# XL_N76E003K1__POWER_V17.net
KiCad netlist of a schematic drawn in Altium Designer
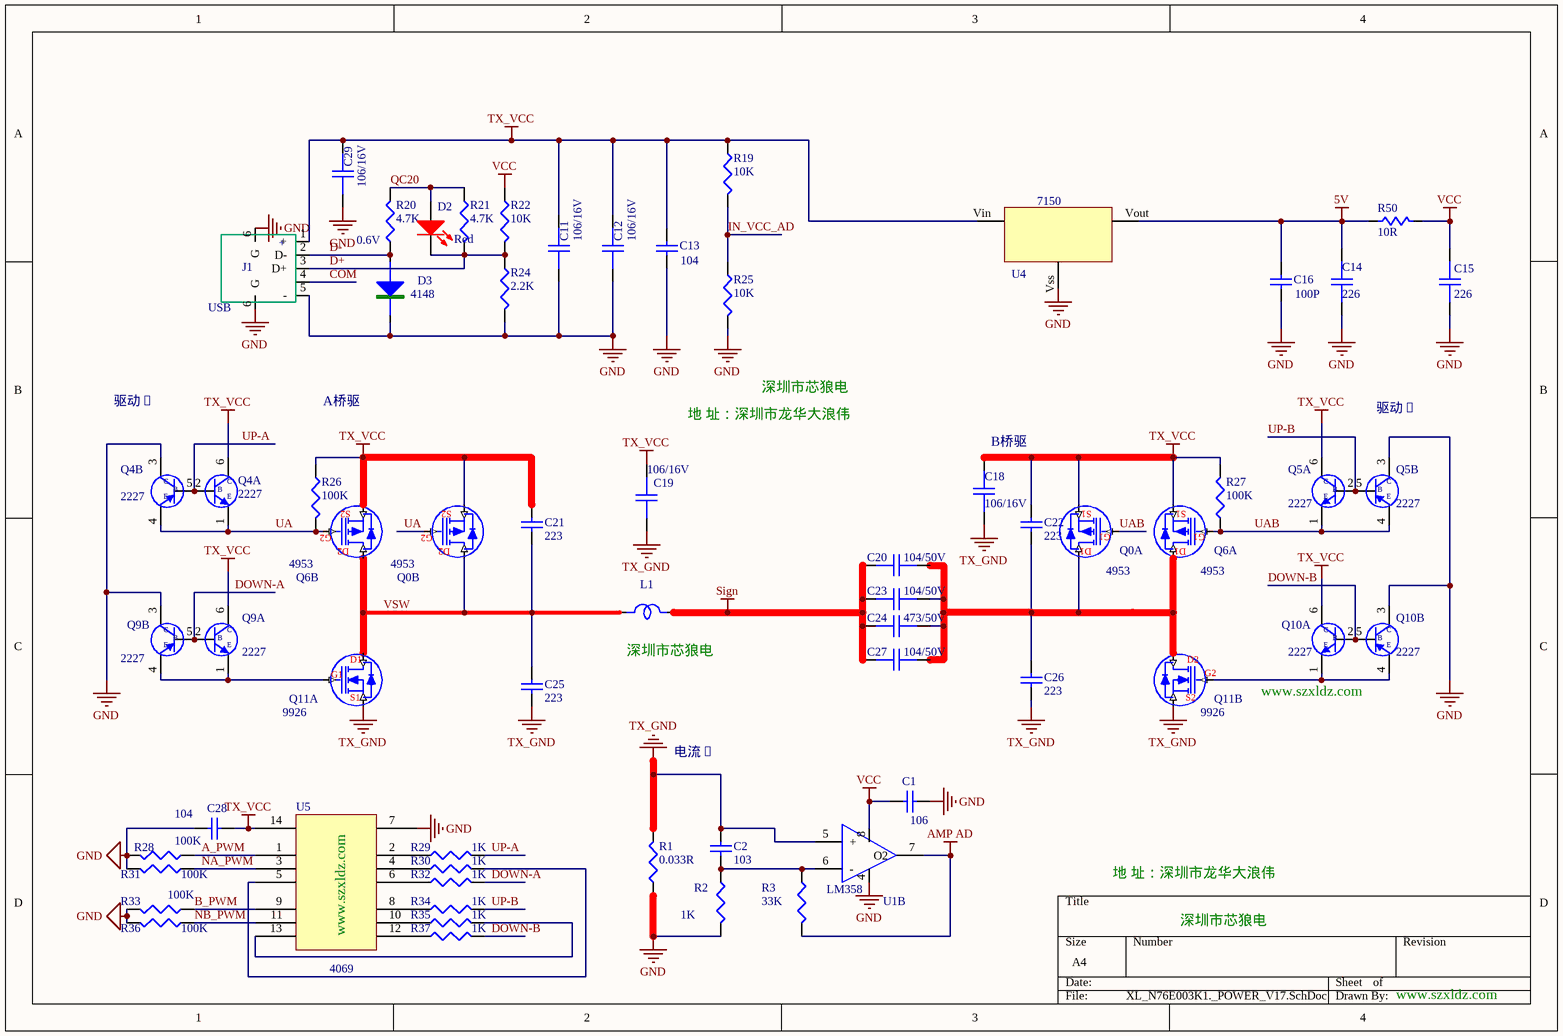
[diagram p0: XL_N76E003K1._POWER_V17.SchDoc]

(export (version "E")
  (design (tool "Eeschema 10.0.6"))
  (components
    (comp (ref "C1")
      (value "106")
      (footprint "C0603")
      (description "Capacitor")
      (fields (field (name "PUBLISHER") "Altium Limited"))
      (libsource (lib "*") (part "Cap"))
    )
    (comp (ref "C2")
      (value "103")
      (footprint "C0402")
      (description "Capacitor")
      (fields (field (name "PUBLISHER") "Altium Limited"))
      (libsource (lib "*") (part "Cap"))
    )
    (comp (ref "C11") (value "106/16V") (footprint "C0805") (libsource (lib "*") (part "CH")))
    (comp (ref "C12") (value "106/16V") (footprint "C0805") (libsource (lib "*") (part "CH")))
    (comp (ref "C13")
      (value "104")
      (footprint "C0402")
      (description "Capacitor")
      (fields (field (name "PUBLISHER") "Altium Limited"))
      (libsource (lib "*") (part "Cap"))
    )
    (comp (ref "C14") (value "226") (footprint "C0805") (libsource (lib "*") (part "CH")))
    (comp (ref "C15") (value "226") (footprint "C0805") (libsource (lib "*") (part "CH")))
    (comp (ref "C16")
      (value "100P")
      (footprint "C0402")
      (description "Capacitor")
      (fields (field (name "PUBLISHER") "Altium Limited"))
      (libsource (lib "*") (part "Cap"))
    )
    (comp (ref "C18") (value "106/16V") (footprint "C0805") (libsource (lib "*") (part "CH")))
    (comp (ref "C19") (value "106/16V") (footprint "C0805") (libsource (lib "*") (part "CH")))
    (comp (ref "C20") (value "104/50V") (footprint "C1206") (libsource (lib "*") (part "CH")))
    (comp (ref "C21")
      (value "223")
      (footprint "C0603")
      (description "Capacitor")
      (fields (field (name "PUBLISHER") "Altium Limited"))
      (libsource (lib "*") (part "Cap"))
    )
    (comp (ref "C22")
      (value "223")
      (footprint "C0603")
      (description "Capacitor")
      (fields (field (name "PUBLISHER") "Altium Limited"))
      (libsource (lib "*") (part "Cap"))
    )
    (comp (ref "C23") (value "104/50V") (footprint "C1206") (libsource (lib "*") (part "CH")))
    (comp (ref "C24") (value "473/50V") (footprint "C1206") (libsource (lib "*") (part "CH")))
    (comp (ref "C25")
      (value "223")
      (footprint "C1206")
      (description "Capacitor")
      (fields (field (name "PUBLISHER") "Altium Limited"))
      (libsource (lib "*") (part "Cap"))
    )
    (comp (ref "C26")
      (value "223")
      (footprint "C0603")
      (description "Capacitor")
      (fields (field (name "PUBLISHER") "Altium Limited"))
      (libsource (lib "*") (part "Cap"))
    )
    (comp (ref "C27") (value "104/50V") (footprint "C1206") (libsource (lib "*") (part "CH")))
    (comp (ref "C28")
      (value "104")
      (footprint "C0402")
      (description "Capacitor")
      (fields (field (name "PUBLISHER") "Altium Limited"))
      (libsource (lib "*") (part "Cap"))
    )
    (comp (ref "C29") (value "106/16V") (footprint "C0805") (libsource (lib "*") (part "CH")))
    (comp (ref "D2") (value "Red") (footprint "LED0603") (libsource (lib "XiaoQiang") (part "LED02")))
    (comp (ref "D3")
      (value "4148")
      (footprint "SOD323")
      (description "1N4001")
      (libsource (lib "*") (part "D0"))
    )
    (comp (ref "J1") (value "USB") (footprint "USB MRO04") (libsource (lib "lxzschlib") (part "USB5P")))
    (comp (ref "L1") (value "~") (footprint "l5mm") (description "1uH") (libsource (lib "*") (part "L")))
    (comp (ref "Q0") (value "4953") (footprint "SOP8D") (libsource (lib "lxzschlib") (part "MOSFETP2")))
    (comp (ref "Q4") (value "2227") (footprint "SOT363") (libsource (lib "lxzschlib") (part "N+PS")))
    (comp (ref "Q5") (value "2227") (footprint "SOT363") (libsource (lib "") (part "N+PS_1")))
    (comp (ref "Q6") (value "4953") (footprint "SOP8D") (libsource (lib "lxzschlib") (part "MOSFETP2")))
    (comp (ref "Q9") (value "2227") (footprint "SOT363") (libsource (lib "lxzschlib") (part "N+PS")))
    (comp (ref "Q10") (value "2227") (footprint "SOT363") (libsource (lib "") (part "N+PS_1")))
    (comp (ref "Q11") (value "9926") (footprint "SOP8D") (libsource (lib "lxzschlib") (part "MOSFETN2")))
    (comp (ref "R1") (value "0.033R") (footprint "R0805") (description "1K") (libsource (lib "*") (part "R")))
    (comp (ref "R2") (value "1K") (footprint "R0402") (libsource (lib "*") (part "R")))
    (comp (ref "R3") (value "33K") (footprint "R0402") (description "1K") (libsource (lib "*") (part "R")))
    (comp (ref "R19") (value "10K") (footprint "R0402") (description "1K") (libsource (lib "*") (part "R")))
    (comp (ref "R20") (value "4.7K") (footprint "R0402") (description "1K") (libsource (lib "*") (part "R")))
    (comp (ref "R21") (value "4.7K") (footprint "R0402") (description "1K") (libsource (lib "*") (part "R")))
    (comp (ref "R22") (value "10K") (footprint "R0402") (description "1K") (libsource (lib "*") (part "R")))
    (comp (ref "R24") (value "2.2K") (footprint "R0402") (description "1K") (libsource (lib "*") (part "R")))
    (comp (ref "R25") (value "10K") (footprint "R0402") (description "1K") (libsource (lib "*") (part "R")))
    (comp (ref "R26") (value "100K") (footprint "R0402") (description "1K") (libsource (lib "*") (part "R")))
    (comp (ref "R27") (value "100K") (footprint "R0402") (description "1K") (libsource (lib "*") (part "R")))
    (comp (ref "R28") (value "100K") (footprint "R0402") (description "1K") (libsource (lib "*") (part "R")))
    (comp (ref "R29") (value "1K") (footprint "R0402") (libsource (lib "*") (part "R")))
    (comp (ref "R30") (value "1K") (footprint "R0402") (libsource (lib "*") (part "R")))
    (comp (ref "R31") (value "100K") (footprint "R0402") (description "1K") (libsource (lib "*") (part "R")))
    (comp (ref "R32") (value "1K") (footprint "R0402") (libsource (lib "*") (part "R")))
    (comp (ref "R33") (value "100K") (footprint "R0402") (description "1K") (libsource (lib "*") (part "R")))
    (comp (ref "R34") (value "1K") (footprint "R0402") (libsource (lib "*") (part "R")))
    (comp (ref "R35") (value "1K") (footprint "R0402") (libsource (lib "*") (part "R")))
    (comp (ref "R36") (value "100K") (footprint "R0402") (description "1K") (libsource (lib "*") (part "R")))
    (comp (ref "R37") (value "1K") (footprint "R0402") (libsource (lib "*") (part "R")))
    (comp (ref "R50") (value "10R") (footprint "R0402") (libsource (lib "Xin Lang") (part "Res01")))
    (comp (ref "U1") (value "LM358") (footprint "SOP8") (libsource (lib "lxzschlib") (part "4558")))
    (comp (ref "U4") (value "7150") (footprint "SOT89a") (libsource (lib "*") (part "VOLTREG")))
    (comp (ref "U5") (value "4069") (footprint "SOP14") (libsource (lib "Schlib1") (part "CD4069")))
  )
  (nets
    (net (code "1") (name "/A_PWM") (class "Default")
      (node (ref "R28") (pin "1") (pintype "passive"))
      (node (ref "U5") (pin "1") (pintype "passive"))
    )
    (net (code "2") (name "/B_PWM") (class "Default")
      (node (ref "R33") (pin "1") (pintype "passive"))
      (node (ref "U5") (pin "9") (pintype "passive"))
    )
    (net (code "3") (name "/COM") (class "Default") (node (ref "J1") (pin "4") (pintype "passive")))
    (net (code "4") (name "/D+") (class "Default")
      (node (ref "D2") (pin "2") (pinfunction "K_2") (pintype "passive"))
      (node (ref "J1") (pin "3") (pinfunction "D+_3") (pintype "passive"))
      (node (ref "R21") (pin "1") (pintype "passive"))
      (node (ref "R22") (pin "1") (pintype "passive"))
      (node (ref "R24") (pin "2") (pintype "passive"))
    )
    (net (code "5") (name "/D-") (class "Default")
      (node (ref "D3") (pin "1") (pintype "passive"))
      (node (ref "J1") (pin "2") (pinfunction "D-_2") (pintype "passive"))
      (node (ref "R20") (pin "2") (pintype "passive"))
    )
    (net (code "6") (name "/DOWN-A") (class "Default")
      (node (ref "Q9") (pin "2") (pinfunction "B_2") (pintype "passive"))
      (node (ref "Q9") (pin "5") (pinfunction "B_5") (pintype "passive"))
      (node (ref "R32") (pin "2") (pintype "passive"))
    )
    (net (code "7") (name "/DOWN-B") (class "Default")
      (node (ref "Q10") (pin "2") (pinfunction "B_2") (pintype "passive"))
      (node (ref "Q10") (pin "5") (pinfunction "B_5") (pintype "passive"))
      (node (ref "R37") (pin "2") (pintype "passive"))
    )
    (net (code "8") (name "/IN_VCC_AD") (class "Default")
      (node (ref "R19") (pin "1") (pintype "passive"))
      (node (ref "R25") (pin "2") (pintype "passive"))
    )
    (net (code "9") (name "/NA_PWM") (class "Default")
      (node (ref "R31") (pin "1") (pintype "passive"))
      (node (ref "U5") (pin "3") (pintype "passive"))
    )
    (net (code "10") (name "/NB_PWM") (class "Default")
      (node (ref "R36") (pin "1") (pintype "passive"))
      (node (ref "U5") (pin "11") (pintype "passive"))
    )
    (net (code "11") (name "/QC20") (class "Default")
      (node (ref "D2") (pin "1") (pinfunction "A_1") (pintype "passive"))
      (node (ref "R20") (pin "1") (pintype "passive"))
      (node (ref "R21") (pin "2") (pintype "passive"))
    )
    (net (code "12") (name "/UA") (class "Default")
      (node (ref "Q0") (pin "B2") (pinfunction "G2_B2") (pintype "input"))
      (node (ref "Q4") (pin "1") (pinfunction "E_1") (pintype "passive"))
      (node (ref "Q4") (pin "4") (pinfunction "E_4") (pintype "passive"))
      (node (ref "Q6") (pin "B2") (pinfunction "G2_B2") (pintype "input"))
      (node (ref "R26") (pin "2") (pintype "passive"))
    )
    (net (code "13") (name "/UAB") (class "Default")
      (node (ref "Q0") (pin "B1") (pinfunction "G1_B1") (pintype "input"))
      (node (ref "Q5") (pin "1") (pinfunction "E_1") (pintype "passive"))
      (node (ref "Q5") (pin "4") (pinfunction "E_4") (pintype "passive"))
      (node (ref "Q6") (pin "B1") (pinfunction "G1_B1") (pintype "input"))
      (node (ref "R27") (pin "1") (pintype "passive"))
    )
    (net (code "14") (name "/UP-A") (class "Default")
      (node (ref "Q4") (pin "2") (pinfunction "B_2") (pintype "passive"))
      (node (ref "Q4") (pin "5") (pinfunction "B_5") (pintype "passive"))
      (node (ref "R29") (pin "2") (pintype "passive"))
    )
    (net (code "15") (name "/UP-B") (class "Default")
      (node (ref "Q5") (pin "2") (pinfunction "B_2") (pintype "passive"))
      (node (ref "Q5") (pin "5") (pinfunction "B_5") (pintype "passive"))
      (node (ref "R34") (pin "2") (pintype "passive"))
    )
    (net (code "16") (name "/VSW") (class "Default")
      (node (ref "C21") (pin "1") (pinfunction "1_1") (pintype "passive"))
      (node (ref "C25") (pin "2") (pinfunction "2_2") (pintype "passive"))
      (node (ref "L1") (pin "1") (pintype "passive"))
      (node (ref "Q0") (pin "C2") (pinfunction "D2_C2") (pintype "input"))
      (node (ref "Q11") (pin "C1") (pinfunction "D1_C1") (pintype "input"))
      (node (ref "Q6") (pin "C2") (pinfunction "D2_C2") (pintype "input"))
    )
    (net (code "17") (name "5V") (class "Default")
      (node (ref "C14") (pin "1") (pintype "passive"))
      (node (ref "C16") (pin "1") (pinfunction "1_1") (pintype "passive"))
      (node (ref "R50") (pin "1") (pinfunction "1_1") (pintype "passive"))
      (node (ref "U4") (pin "Vout") (pintype "passive"))
    )
    (net (code "18") (name "AMP AD") (class "Default")
      (node (ref "R3") (pin "2") (pintype "passive"))
      (node (ref "U1") (pin "7") (pinfunction "O2_7") (pintype "passive"))
    )
    (net (code "19") (name "GND") (class "Default")
      (node (ref "C1") (pin "1") (pinfunction "1_1") (pintype "passive"))
      (node (ref "C11") (pin "2") (pintype "passive"))
      (node (ref "C12") (pin "2") (pintype "passive"))
      (node (ref "C13") (pin "2") (pinfunction "2_2") (pintype "passive"))
      (node (ref "C14") (pin "2") (pintype "passive"))
      (node (ref "C15") (pin "1") (pintype "passive"))
      (node (ref "C16") (pin "2") (pinfunction "2_2") (pintype "passive"))
      (node (ref "C28") (pin "1") (pinfunction "1_1") (pintype "passive"))
      (node (ref "C29") (pin "2") (pintype "passive"))
      (node (ref "D3") (pin "2") (pintype "passive"))
      (node (ref "J1") (pin "5") (pinfunction "-_5") (pintype "passive"))
      (node (ref "J1") (pin "6") (pinfunction "G_6") (pintype "passive"))
      (node (ref "Q10") (pin "3") (pinfunction "C_3") (pintype "passive"))
      (node (ref "Q4") (pin "3") (pinfunction "C_3") (pintype "passive"))
      (node (ref "Q5") (pin "3") (pinfunction "C_3") (pintype "passive"))
      (node (ref "Q9") (pin "3") (pinfunction "C_3") (pintype "passive"))
      (node (ref "R1") (pin "1") (pintype "passive"))
      (node (ref "R2") (pin "2") (pintype "passive"))
      (node (ref "R24") (pin "1") (pintype "passive"))
      (node (ref "R25") (pin "1") (pintype "passive"))
      (node (ref "R28") (pin "2") (pintype "passive"))
      (node (ref "R31") (pin "2") (pintype "passive"))
      (node (ref "R33") (pin "2") (pintype "passive"))
      (node (ref "R36") (pin "2") (pintype "passive"))
      (node (ref "U1") (pin "4") (pintype "passive"))
      (node (ref "U4") (pin "Vss") (pintype "passive"))
      (node (ref "U5") (pin "7") (pintype "passive"))
    )
    (net (code "20") (name "Net-(Q0A-D1)") (class "Default")
      (node (ref "C20") (pin "2") (pintype "passive"))
      (node (ref "C22") (pin "1") (pinfunction "1_1") (pintype "passive"))
      (node (ref "C23") (pin "2") (pintype "passive"))
      (node (ref "C24") (pin "2") (pintype "passive"))
      (node (ref "C26") (pin "2") (pinfunction "2_2") (pintype "passive"))
      (node (ref "C27") (pin "2") (pintype "passive"))
      (node (ref "Q0") (pin "C1") (pinfunction "D1_C1") (pintype "input"))
      (node (ref "Q11") (pin "C2") (pinfunction "D2_C2") (pintype "input"))
      (node (ref "Q6") (pin "C1") (pinfunction "D1_C1") (pintype "input"))
    )
    (net (code "21") (name "Net-(Q10A-E)") (class "Default")
      (node (ref "Q10") (pin "1") (pinfunction "E_1") (pintype "passive"))
      (node (ref "Q10") (pin "4") (pinfunction "E_4") (pintype "passive"))
      (node (ref "Q11") (pin "B2") (pinfunction "G2_B2") (pintype "input"))
    )
    (net (code "22") (name "Net-(Q11A-G1)") (class "Default")
      (node (ref "Q11") (pin "B1") (pinfunction "G1_B1") (pintype "input"))
      (node (ref "Q9") (pin "1") (pinfunction "E_1") (pintype "passive"))
      (node (ref "Q9") (pin "4") (pinfunction "E_4") (pintype "passive"))
    )
    (net (code "23") (name "Net-(R29-Pad1)") (class "Default")
      (node (ref "R29") (pin "1") (pintype "passive"))
      (node (ref "U5") (pin "2") (pintype "passive"))
    )
    (net (code "24") (name "Net-(R30-Pad1)") (class "Default")
      (node (ref "R30") (pin "1") (pintype "passive"))
      (node (ref "U5") (pin "4") (pintype "passive"))
    )
    (net (code "25") (name "Net-(R30-Pad2)") (class "Default")
      (node (ref "R30") (pin "2") (pintype "passive"))
      (node (ref "U5") (pin "5") (pintype "passive"))
    )
    (net (code "26") (name "Net-(R32-Pad1)") (class "Default")
      (node (ref "R32") (pin "1") (pintype "passive"))
      (node (ref "U5") (pin "6") (pintype "passive"))
    )
    (net (code "27") (name "Net-(R34-Pad1)") (class "Default")
      (node (ref "R34") (pin "1") (pintype "passive"))
      (node (ref "U5") (pin "8") (pintype "passive"))
    )
    (net (code "28") (name "Net-(R35-Pad1)") (class "Default")
      (node (ref "R35") (pin "1") (pintype "passive"))
      (node (ref "U5") (pin "10") (pintype "passive"))
    )
    (net (code "29") (name "Net-(R35-Pad2)") (class "Default")
      (node (ref "R35") (pin "2") (pintype "passive"))
      (node (ref "U5") (pin "13") (pintype "passive"))
    )
    (net (code "30") (name "Net-(R37-Pad1)") (class "Default")
      (node (ref "R37") (pin "1") (pintype "passive"))
      (node (ref "U5") (pin "12") (pintype "passive"))
    )
    (net (code "31") (name "Net-(U1B--)") (class "Default")
      (node (ref "C2") (pin "2") (pinfunction "2_2") (pintype "passive"))
      (node (ref "R2") (pin "1") (pintype "passive"))
      (node (ref "R3") (pin "1") (pintype "passive"))
      (node (ref "U1") (pin "6") (pinfunction "-_6") (pintype "passive"))
    )
    (net (code "32") (name "Sign") (class "Default")
      (node (ref "C20") (pin "1") (pintype "passive"))
      (node (ref "C23") (pin "1") (pintype "passive"))
      (node (ref "C24") (pin "1") (pintype "passive"))
      (node (ref "C27") (pin "1") (pintype "passive"))
      (node (ref "L1") (pin "2") (pintype "passive"))
    )
    (net (code "33") (name "TX_GND") (class "Default")
      (node (ref "C18") (pin "2") (pintype "passive"))
      (node (ref "C19") (pin "2") (pintype "passive"))
      (node (ref "C2") (pin "1") (pinfunction "1_1") (pintype "passive"))
      (node (ref "C25") (pin "1") (pinfunction "1_1") (pintype "passive"))
      (node (ref "C26") (pin "1") (pinfunction "1_1") (pintype "passive"))
      (node (ref "Q11") (pin "E1") (pinfunction "S1_E1") (pintype "input"))
      (node (ref "Q11") (pin "E2") (pinfunction "S2_E2") (pintype "input"))
      (node (ref "R1") (pin "2") (pintype "passive"))
      (node (ref "U1") (pin "5") (pinfunction "+_5") (pintype "passive"))
    )
    (net (code "34") (name "TX_VCC") (class "Default")
      (node (ref "C11") (pin "1") (pintype "passive"))
      (node (ref "C12") (pin "1") (pintype "passive"))
      (node (ref "C13") (pin "1") (pinfunction "1_1") (pintype "passive"))
      (node (ref "C18") (pin "1") (pintype "passive"))
      (node (ref "C19") (pin "1") (pintype "passive"))
      (node (ref "C21") (pin "2") (pinfunction "2_2") (pintype "passive"))
      (node (ref "C22") (pin "2") (pinfunction "2_2") (pintype "passive"))
      (node (ref "C28") (pin "2") (pinfunction "2_2") (pintype "passive"))
      (node (ref "C29") (pin "1") (pintype "passive"))
      (node (ref "J1") (pin "1") (pinfunction "+_1") (pintype "passive"))
      (node (ref "Q0") (pin "E1") (pinfunction "S1_E1") (pintype "input"))
      (node (ref "Q0") (pin "E2") (pinfunction "S2_E2") (pintype "input"))
      (node (ref "Q10") (pin "6") (pinfunction "C_6") (pintype "passive"))
      (node (ref "Q4") (pin "6") (pinfunction "C_6") (pintype "passive"))
      (node (ref "Q5") (pin "6") (pinfunction "C_6") (pintype "passive"))
      (node (ref "Q6") (pin "E1") (pinfunction "S1_E1") (pintype "input"))
      (node (ref "Q6") (pin "E2") (pinfunction "S2_E2") (pintype "input"))
      (node (ref "Q9") (pin "6") (pinfunction "C_6") (pintype "passive"))
      (node (ref "R19") (pin "2") (pintype "passive"))
      (node (ref "R26") (pin "1") (pintype "passive"))
      (node (ref "R27") (pin "2") (pintype "passive"))
      (node (ref "U4") (pin "Vin") (pintype "passive"))
      (node (ref "U5") (pin "14") (pintype "passive"))
    )
    (net (code "35") (name "VCC") (class "Default")
      (node (ref "C1") (pin "2") (pinfunction "2_2") (pintype "passive"))
      (node (ref "C15") (pin "2") (pintype "passive"))
      (node (ref "R22") (pin "2") (pintype "passive"))
      (node (ref "R50") (pin "2") (pinfunction "2_2") (pintype "passive"))
      (node (ref "U1") (pin "8") (pintype "passive"))
    )
  )
)
